# IPNS_v0_1.net
KiCad netlist of a schematic drawn in EAGLE
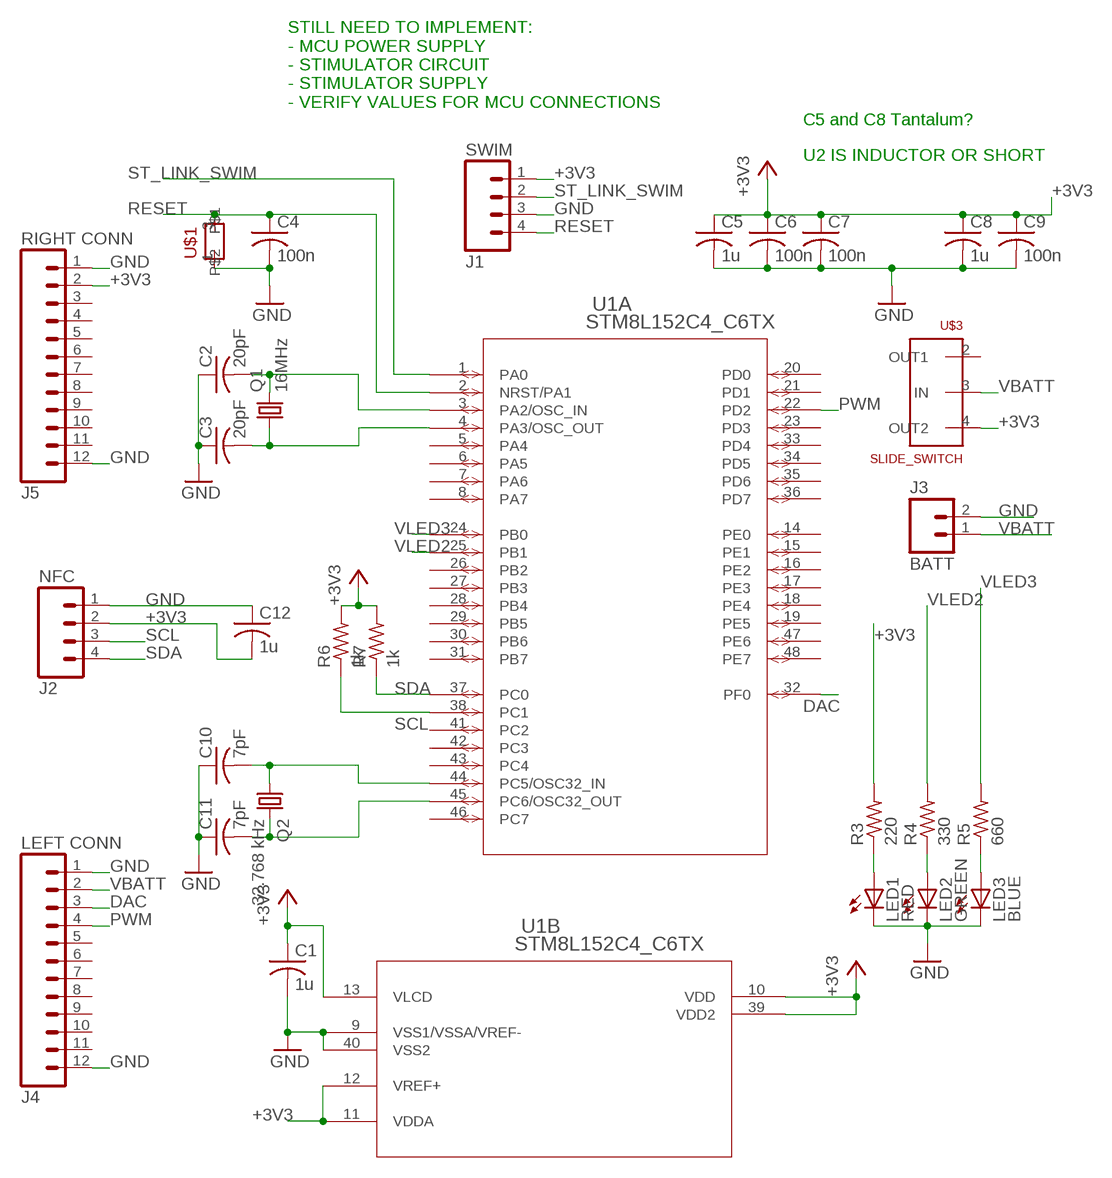
[diagram p0: schematic, sheet 1]

(export (version "E")
  (design (tool "Eeschema 10.0.6"))
  (components
    (comp (ref "C1")
      (value "1u")
      (footprint "eagle-import:C0805")
      (libsource (lib "eagle-import") (part "C-USC0805"))
    )
    (comp (ref "C2")
      (value "20pF")
      (footprint "eagle-import:C0805")
      (libsource (lib "eagle-import") (part "C-USC0805"))
    )
    (comp (ref "C3")
      (value "20pF")
      (footprint "eagle-import:C0805")
      (libsource (lib "eagle-import") (part "C-USC0805"))
    )
    (comp (ref "C4")
      (value "100n")
      (footprint "eagle-import:C0805")
      (libsource (lib "eagle-import") (part "C-USC0805"))
    )
    (comp (ref "C5")
      (value "1u")
      (footprint "eagle-import:C0805")
      (libsource (lib "eagle-import") (part "C-USC0805"))
    )
    (comp (ref "C6")
      (value "100n")
      (footprint "eagle-import:C0805")
      (libsource (lib "eagle-import") (part "C-USC0805"))
    )
    (comp (ref "C7")
      (value "100n")
      (footprint "eagle-import:C0805")
      (libsource (lib "eagle-import") (part "C-USC0805"))
    )
    (comp (ref "C8")
      (value "1u")
      (footprint "eagle-import:C0805")
      (libsource (lib "eagle-import") (part "C-USC0805"))
    )
    (comp (ref "C9")
      (value "100n")
      (footprint "eagle-import:C0805")
      (libsource (lib "eagle-import") (part "C-USC0805"))
    )
    (comp (ref "C10")
      (value "7pF")
      (footprint "eagle-import:C0805")
      (libsource (lib "eagle-import") (part "C-USC0805"))
    )
    (comp (ref "C11")
      (value "7pF")
      (footprint "eagle-import:C0805")
      (libsource (lib "eagle-import") (part "C-USC0805"))
    )
    (comp (ref "C12")
      (value "1u")
      (footprint "eagle-import:C0805")
      (libsource (lib "eagle-import") (part "C-USC0805"))
    )
    (comp (ref "J1")
      (value "SWIM")
      (footprint "eagle-import:1X04")
      (libsource (lib "eagle-import") (part "M04PTH"))
    )
    (comp (ref "J2")
      (value "NFC")
      (footprint "eagle-import:1X04")
      (libsource (lib "eagle-import") (part "M04PTH"))
    )
    (comp (ref "J3")
      (value "BATT")
      (footprint "eagle-import:1X02")
      (libsource (lib "eagle-import") (part "M02PTH"))
    )
    (comp (ref "J4")
      (value "LEFT CONN")
      (footprint "eagle-import:1X12")
      (libsource (lib "eagle-import") (part "M12PTH"))
    )
    (comp (ref "J5")
      (value "RIGHT CONN")
      (footprint "eagle-import:1X12")
      (libsource (lib "eagle-import") (part "M12PTH"))
    )
    (comp (ref "LED1")
      (value "RED")
      (footprint "eagle-import:CHIP-LED0805")
      (libsource (lib "eagle-import") (part "LEDCHIP-LED0805"))
    )
    (comp (ref "LED2")
      (value "GREEN")
      (footprint "eagle-import:CHIP-LED0805")
      (libsource (lib "eagle-import") (part "LEDCHIP-LED0805"))
    )
    (comp (ref "LED3")
      (value "BLUE")
      (footprint "eagle-import:CHIP-LED0805")
      (libsource (lib "eagle-import") (part "LEDCHIP-LED0805"))
    )
    (comp (ref "Q1")
      (value "16MHz")
      (footprint "eagle-import:HC49_S")
      (libsource (lib "eagle-import") (part "CRYSTALHC49S"))
    )
    (comp (ref "Q2")
      (value "32.768 kHz")
      (footprint "eagle-import:TC26H")
      (libsource (lib "eagle-import") (part "CRYSTALTC26H"))
    )
    (comp (ref "R3")
      (value "220")
      (footprint "eagle-import:R0805")
      (libsource (lib "eagle-import") (part "R-US_R0805"))
    )
    (comp (ref "R4")
      (value "330")
      (footprint "eagle-import:R0805")
      (libsource (lib "eagle-import") (part "R-US_R0805"))
    )
    (comp (ref "R5")
      (value "660")
      (footprint "eagle-import:R0805")
      (libsource (lib "eagle-import") (part "R-US_R0805"))
    )
    (comp (ref "R6")
      (value "1k")
      (footprint "eagle-import:R0805")
      (libsource (lib "eagle-import") (part "R-US_R0805"))
    )
    (comp (ref "R7")
      (value "1k")
      (footprint "eagle-import:R0805")
      (libsource (lib "eagle-import") (part "R-US_R0805"))
    )
    (comp (ref "U$1")
      (value "PUSH-BUTTON")
      (footprint "eagle-import:PUSH-BUTTON")
      (libsource (lib "eagle-import") (part "PUSH-BUTTON"))
    )
    (comp (ref "U$3")
      (value "SLIDE_SWITCH")
      (footprint "eagle-import:SLIDE_SWITCH")
      (libsource (lib "eagle-import") (part "SLIDE_SWITCH"))
    )
    (comp (ref "U1")
      (value "STM8L152C4_C6TX")
      (footprint "eagle-import:LQFP48-7X7MM")
      (fields
        (field (name "MANUFACTURER_PART_NUMBER") "stm8l152c4_c6tx")
        (field (name "COPYRIGHT") "Copyright (C) 2016 Accelerated Designs. All rights reserved")
      )
      (libsource (lib "eagle-import") (part "STM8L152C4_C6TX"))
    )
  )
  (nets
    (net (code "1") (name "+3V3") (class "Default")
      (node (ref "C1") (pin "1") (pinfunction "1_1") (pintype "passive"))
      (node (ref "C12") (pin "2") (pinfunction "2_2") (pintype "passive"))
      (node (ref "C5") (pin "1") (pinfunction "1_1") (pintype "passive"))
      (node (ref "C6") (pin "1") (pinfunction "1_1") (pintype "passive"))
      (node (ref "C7") (pin "1") (pinfunction "1_1") (pintype "passive"))
      (node (ref "C8") (pin "1") (pinfunction "1_1") (pintype "passive"))
      (node (ref "C9") (pin "1") (pinfunction "1_1") (pintype "passive"))
      (node (ref "J1") (pin "1") (pinfunction "1_1") (pintype "passive"))
      (node (ref "J2") (pin "2") (pinfunction "2_2") (pintype "passive"))
      (node (ref "J5") (pin "2") (pinfunction "2_2") (pintype "passive"))
      (node (ref "R3") (pin "2") (pinfunction "2_2") (pintype "passive"))
      (node (ref "R6") (pin "2") (pinfunction "2_2") (pintype "passive"))
      (node (ref "R7") (pin "2") (pinfunction "2_2") (pintype "passive"))
      (node (ref "U$3") (pin "4") (pinfunction "OUT2_4") (pintype "bidirectional"))
      (node (ref "U1") (pin "10") (pinfunction "VDD_10") (pintype "power_in"))
      (node (ref "U1") (pin "11") (pinfunction "VDDA_11") (pintype "power_in"))
      (node (ref "U1") (pin "12") (pinfunction "VREF+_12") (pintype "power_in"))
      (node (ref "U1") (pin "13") (pinfunction "VLCD_13") (pintype "power_in"))
      (node (ref "U1") (pin "39") (pinfunction "VDD2_39") (pintype "power_in"))
    )
    (net (code "2") (name "/DAC") (class "Default")
      (node (ref "J4") (pin "3") (pinfunction "3_3") (pintype "passive"))
      (node (ref "U1") (pin "32") (pinfunction "PF0_32") (pintype "bidirectional"))
    )
    (net (code "3") (name "/PWM") (class "Default")
      (node (ref "J4") (pin "4") (pinfunction "4_4") (pintype "passive"))
      (node (ref "U1") (pin "22") (pinfunction "PD2_22") (pintype "bidirectional"))
    )
    (net (code "4") (name "/RESET") (class "Default")
      (node (ref "C4") (pin "1") (pinfunction "1_1") (pintype "passive"))
      (node (ref "J1") (pin "4") (pinfunction "4_4") (pintype "passive"))
      (node (ref "U$1") (pin "3") (pinfunction "P$2_3") (pintype "bidirectional"))
      (node (ref "U1") (pin "2") (pinfunction "NRST/PA1_2") (pintype "bidirectional"))
    )
    (net (code "5") (name "/SCL") (class "Default")
      (node (ref "J2") (pin "3") (pinfunction "3_3") (pintype "passive"))
      (node (ref "R6") (pin "1") (pinfunction "1_1") (pintype "passive"))
      (node (ref "U1") (pin "38") (pinfunction "PC1_38") (pintype "bidirectional"))
    )
    (net (code "6") (name "/SDA") (class "Default")
      (node (ref "J2") (pin "4") (pinfunction "4_4") (pintype "passive"))
      (node (ref "R7") (pin "1") (pinfunction "1_1") (pintype "passive"))
      (node (ref "U1") (pin "37") (pinfunction "PC0_37") (pintype "bidirectional"))
    )
    (net (code "7") (name "/ST_LINK_SWIM") (class "Default")
      (node (ref "J1") (pin "2") (pinfunction "2_2") (pintype "passive"))
      (node (ref "U1") (pin "1") (pinfunction "PA0_1") (pintype "bidirectional"))
    )
    (net (code "8") (name "/VBATT") (class "Default")
      (node (ref "J3") (pin "1") (pinfunction "1_1") (pintype "passive"))
      (node (ref "J4") (pin "2") (pinfunction "2_2") (pintype "passive"))
      (node (ref "U$3") (pin "3") (pinfunction "IN_3") (pintype "bidirectional"))
    )
    (net (code "9") (name "/VLED2") (class "Default")
      (node (ref "R4") (pin "2") (pinfunction "2_2") (pintype "passive"))
      (node (ref "U1") (pin "25") (pinfunction "PB1_25") (pintype "bidirectional"))
    )
    (net (code "10") (name "/VLED3") (class "Default")
      (node (ref "R5") (pin "2") (pinfunction "2_2") (pintype "passive"))
      (node (ref "U1") (pin "24") (pinfunction "PB0_24") (pintype "bidirectional"))
    )
    (net (code "11") (name "GND") (class "Default")
      (node (ref "C1") (pin "2") (pinfunction "2_2") (pintype "passive"))
      (node (ref "C10") (pin "1") (pinfunction "1_1") (pintype "passive"))
      (node (ref "C11") (pin "1") (pinfunction "1_1") (pintype "passive"))
      (node (ref "C12") (pin "1") (pinfunction "1_1") (pintype "passive"))
      (node (ref "C2") (pin "1") (pinfunction "1_1") (pintype "passive"))
      (node (ref "C3") (pin "1") (pinfunction "1_1") (pintype "passive"))
      (node (ref "C4") (pin "2") (pinfunction "2_2") (pintype "passive"))
      (node (ref "C5") (pin "2") (pinfunction "2_2") (pintype "passive"))
      (node (ref "C6") (pin "2") (pinfunction "2_2") (pintype "passive"))
      (node (ref "C7") (pin "2") (pinfunction "2_2") (pintype "passive"))
      (node (ref "C8") (pin "2") (pinfunction "2_2") (pintype "passive"))
      (node (ref "C9") (pin "2") (pinfunction "2_2") (pintype "passive"))
      (node (ref "J1") (pin "3") (pinfunction "3_3") (pintype "passive"))
      (node (ref "J2") (pin "1") (pinfunction "1_1") (pintype "passive"))
      (node (ref "J3") (pin "2") (pinfunction "2_2") (pintype "passive"))
      (node (ref "J4") (pin "1") (pinfunction "1_1") (pintype "passive"))
      (node (ref "J4") (pin "12") (pinfunction "12_12") (pintype "passive"))
      (node (ref "J5") (pin "1") (pinfunction "1_1") (pintype "passive"))
      (node (ref "J5") (pin "12") (pinfunction "12_12") (pintype "passive"))
      (node (ref "LED1") (pin "C") (pinfunction "C_C") (pintype "passive"))
      (node (ref "LED2") (pin "C") (pinfunction "C_C") (pintype "passive"))
      (node (ref "LED3") (pin "C") (pinfunction "C_C") (pintype "passive"))
      (node (ref "U$1") (pin "1") (pinfunction "P$1_1") (pintype "bidirectional"))
      (node (ref "U1") (pin "40") (pinfunction "VSS2_40") (pintype "power_in"))
      (node (ref "U1") (pin "9") (pinfunction "VSS1/VSSA/VREF-_9") (pintype "power_in"))
    )
    (net (code "12") (name "Net-(LED1-PadA)") (class "Default")
      (node (ref "LED1") (pin "A") (pinfunction "A_A") (pintype "passive"))
      (node (ref "R3") (pin "1") (pinfunction "1_1") (pintype "passive"))
    )
    (net (code "13") (name "Net-(LED2-PadA)") (class "Default")
      (node (ref "LED2") (pin "A") (pinfunction "A_A") (pintype "passive"))
      (node (ref "R4") (pin "1") (pinfunction "1_1") (pintype "passive"))
    )
    (net (code "14") (name "Net-(LED3-PadA)") (class "Default")
      (node (ref "LED3") (pin "A") (pinfunction "A_A") (pintype "passive"))
      (node (ref "R5") (pin "1") (pinfunction "1_1") (pintype "passive"))
    )
    (net (code "15") (name "Net-(U1A-PA2{slash}OSC_IN)") (class "Default")
      (node (ref "C2") (pin "2") (pinfunction "2_2") (pintype "passive"))
      (node (ref "Q1") (pin "2") (pinfunction "2_2") (pintype "passive"))
      (node (ref "U1") (pin "3") (pinfunction "PA2/OSC_IN_3") (pintype "bidirectional"))
    )
    (net (code "16") (name "Net-(U1A-PA3{slash}OSC_OUT)") (class "Default")
      (node (ref "C3") (pin "2") (pinfunction "2_2") (pintype "passive"))
      (node (ref "Q1") (pin "1") (pinfunction "1_1") (pintype "passive"))
      (node (ref "U1") (pin "4") (pinfunction "PA3/OSC_OUT_4") (pintype "bidirectional"))
    )
    (net (code "17") (name "Net-(U1A-PC5{slash}OSC32_IN)") (class "Default")
      (node (ref "C10") (pin "2") (pinfunction "2_2") (pintype "passive"))
      (node (ref "Q2") (pin "1") (pinfunction "1_1") (pintype "passive"))
      (node (ref "U1") (pin "44") (pinfunction "PC5/OSC32_IN_44") (pintype "bidirectional"))
    )
    (net (code "18") (name "Net-(U1A-PC6{slash}OSC32_OUT)") (class "Default")
      (node (ref "C11") (pin "2") (pinfunction "2_2") (pintype "passive"))
      (node (ref "Q2") (pin "2") (pinfunction "2_2") (pintype "passive"))
      (node (ref "U1") (pin "45") (pinfunction "PC6/OSC32_OUT_45") (pintype "bidirectional"))
    )
    (net (code "19") (name "unconnected-(J4-Pad5)") (class "Default")
      (node (ref "J4") (pin "5") (pinfunction "5_5") (pintype "passive"))
    )
    (net (code "20") (name "unconnected-(J4-Pad6)") (class "Default")
      (node (ref "J4") (pin "6") (pinfunction "6_6") (pintype "passive"))
    )
    (net (code "21") (name "unconnected-(J4-Pad7)") (class "Default")
      (node (ref "J4") (pin "7") (pinfunction "7_7") (pintype "passive"))
    )
    (net (code "22") (name "unconnected-(J4-Pad8)") (class "Default")
      (node (ref "J4") (pin "8") (pinfunction "8_8") (pintype "passive"))
    )
    (net (code "23") (name "unconnected-(J4-Pad9)") (class "Default")
      (node (ref "J4") (pin "9") (pinfunction "9_9") (pintype "passive"))
    )
    (net (code "24") (name "unconnected-(J4-Pad10)") (class "Default")
      (node (ref "J4") (pin "10") (pinfunction "10_10") (pintype "passive"))
    )
    (net (code "25") (name "unconnected-(J4-Pad11)") (class "Default")
      (node (ref "J4") (pin "11") (pinfunction "11_11") (pintype "passive"))
    )
    (net (code "26") (name "unconnected-(J5-Pad3)") (class "Default")
      (node (ref "J5") (pin "3") (pinfunction "3_3") (pintype "passive"))
    )
    (net (code "27") (name "unconnected-(J5-Pad4)") (class "Default")
      (node (ref "J5") (pin "4") (pinfunction "4_4") (pintype "passive"))
    )
    (net (code "28") (name "unconnected-(J5-Pad5)") (class "Default")
      (node (ref "J5") (pin "5") (pinfunction "5_5") (pintype "passive"))
    )
    (net (code "29") (name "unconnected-(J5-Pad6)") (class "Default")
      (node (ref "J5") (pin "6") (pinfunction "6_6") (pintype "passive"))
    )
    (net (code "30") (name "unconnected-(J5-Pad7)") (class "Default")
      (node (ref "J5") (pin "7") (pinfunction "7_7") (pintype "passive"))
    )
    (net (code "31") (name "unconnected-(J5-Pad8)") (class "Default")
      (node (ref "J5") (pin "8") (pinfunction "8_8") (pintype "passive"))
    )
    (net (code "32") (name "unconnected-(J5-Pad9)") (class "Default")
      (node (ref "J5") (pin "9") (pinfunction "9_9") (pintype "passive"))
    )
    (net (code "33") (name "unconnected-(J5-Pad10)") (class "Default")
      (node (ref "J5") (pin "10") (pinfunction "10_10") (pintype "passive"))
    )
    (net (code "34") (name "unconnected-(J5-Pad11)") (class "Default")
      (node (ref "J5") (pin "11") (pinfunction "11_11") (pintype "passive"))
    )
    (net (code "35") (name "unconnected-(U$3-OUT1-Pad2)") (class "Default")
      (node (ref "U$3") (pin "2") (pinfunction "OUT1_2") (pintype "bidirectional"))
    )
    (net (code "36") (name "unconnected-(U1A-PA4-Pad5)") (class "Default")
      (node (ref "U1") (pin "5") (pinfunction "PA4_5") (pintype "bidirectional"))
    )
    (net (code "37") (name "unconnected-(U1A-PA5-Pad6)") (class "Default")
      (node (ref "U1") (pin "6") (pinfunction "PA5_6") (pintype "bidirectional"))
    )
    (net (code "38") (name "unconnected-(U1A-PA6-Pad7)") (class "Default")
      (node (ref "U1") (pin "7") (pinfunction "PA6_7") (pintype "bidirectional"))
    )
    (net (code "39") (name "unconnected-(U1A-PA7-Pad8)") (class "Default")
      (node (ref "U1") (pin "8") (pinfunction "PA7_8") (pintype "bidirectional"))
    )
    (net (code "40") (name "unconnected-(U1A-PB2-Pad26)") (class "Default")
      (node (ref "U1") (pin "26") (pinfunction "PB2_26") (pintype "bidirectional"))
    )
    (net (code "41") (name "unconnected-(U1A-PB3-Pad27)") (class "Default")
      (node (ref "U1") (pin "27") (pinfunction "PB3_27") (pintype "bidirectional"))
    )
    (net (code "42") (name "unconnected-(U1A-PB4-Pad28)") (class "Default")
      (node (ref "U1") (pin "28") (pinfunction "PB4_28") (pintype "bidirectional"))
    )
    (net (code "43") (name "unconnected-(U1A-PB5-Pad29)") (class "Default")
      (node (ref "U1") (pin "29") (pinfunction "PB5_29") (pintype "bidirectional"))
    )
    (net (code "44") (name "unconnected-(U1A-PB6-Pad30)") (class "Default")
      (node (ref "U1") (pin "30") (pinfunction "PB6_30") (pintype "bidirectional"))
    )
    (net (code "45") (name "unconnected-(U1A-PB7-Pad31)") (class "Default")
      (node (ref "U1") (pin "31") (pinfunction "PB7_31") (pintype "bidirectional"))
    )
    (net (code "46") (name "unconnected-(U1A-PC2-Pad41)") (class "Default")
      (node (ref "U1") (pin "41") (pinfunction "PC2_41") (pintype "bidirectional"))
    )
    (net (code "47") (name "unconnected-(U1A-PC3-Pad42)") (class "Default")
      (node (ref "U1") (pin "42") (pinfunction "PC3_42") (pintype "bidirectional"))
    )
    (net (code "48") (name "unconnected-(U1A-PC4-Pad43)") (class "Default")
      (node (ref "U1") (pin "43") (pinfunction "PC4_43") (pintype "bidirectional"))
    )
    (net (code "49") (name "unconnected-(U1A-PC7-Pad46)") (class "Default")
      (node (ref "U1") (pin "46") (pinfunction "PC7_46") (pintype "bidirectional"))
    )
    (net (code "50") (name "unconnected-(U1A-PD0-Pad20)") (class "Default")
      (node (ref "U1") (pin "20") (pinfunction "PD0_20") (pintype "bidirectional"))
    )
    (net (code "51") (name "unconnected-(U1A-PD1-Pad21)") (class "Default")
      (node (ref "U1") (pin "21") (pinfunction "PD1_21") (pintype "bidirectional"))
    )
    (net (code "52") (name "unconnected-(U1A-PD3-Pad23)") (class "Default")
      (node (ref "U1") (pin "23") (pinfunction "PD3_23") (pintype "bidirectional"))
    )
    (net (code "53") (name "unconnected-(U1A-PD4-Pad33)") (class "Default")
      (node (ref "U1") (pin "33") (pinfunction "PD4_33") (pintype "bidirectional"))
    )
    (net (code "54") (name "unconnected-(U1A-PD5-Pad34)") (class "Default")
      (node (ref "U1") (pin "34") (pinfunction "PD5_34") (pintype "bidirectional"))
    )
    (net (code "55") (name "unconnected-(U1A-PD6-Pad35)") (class "Default")
      (node (ref "U1") (pin "35") (pinfunction "PD6_35") (pintype "bidirectional"))
    )
    (net (code "56") (name "unconnected-(U1A-PD7-Pad36)") (class "Default")
      (node (ref "U1") (pin "36") (pinfunction "PD7_36") (pintype "bidirectional"))
    )
    (net (code "57") (name "unconnected-(U1A-PE0-Pad14)") (class "Default")
      (node (ref "U1") (pin "14") (pinfunction "PE0_14") (pintype "bidirectional"))
    )
    (net (code "58") (name "unconnected-(U1A-PE1-Pad15)") (class "Default")
      (node (ref "U1") (pin "15") (pinfunction "PE1_15") (pintype "bidirectional"))
    )
    (net (code "59") (name "unconnected-(U1A-PE2-Pad16)") (class "Default")
      (node (ref "U1") (pin "16") (pinfunction "PE2_16") (pintype "bidirectional"))
    )
    (net (code "60") (name "unconnected-(U1A-PE3-Pad17)") (class "Default")
      (node (ref "U1") (pin "17") (pinfunction "PE3_17") (pintype "bidirectional"))
    )
    (net (code "61") (name "unconnected-(U1A-PE4-Pad18)") (class "Default")
      (node (ref "U1") (pin "18") (pinfunction "PE4_18") (pintype "bidirectional"))
    )
    (net (code "62") (name "unconnected-(U1A-PE5-Pad19)") (class "Default")
      (node (ref "U1") (pin "19") (pinfunction "PE5_19") (pintype "bidirectional"))
    )
    (net (code "63") (name "unconnected-(U1A-PE6-Pad47)") (class "Default")
      (node (ref "U1") (pin "47") (pinfunction "PE6_47") (pintype "bidirectional"))
    )
    (net (code "64") (name "unconnected-(U1A-PE7-Pad48)") (class "Default")
      (node (ref "U1") (pin "48") (pinfunction "PE7_48") (pintype "bidirectional"))
    )
  )
)
